# OneWireBus_Interface.net
KiCad netlist of a schematic drawn in Altium Designer
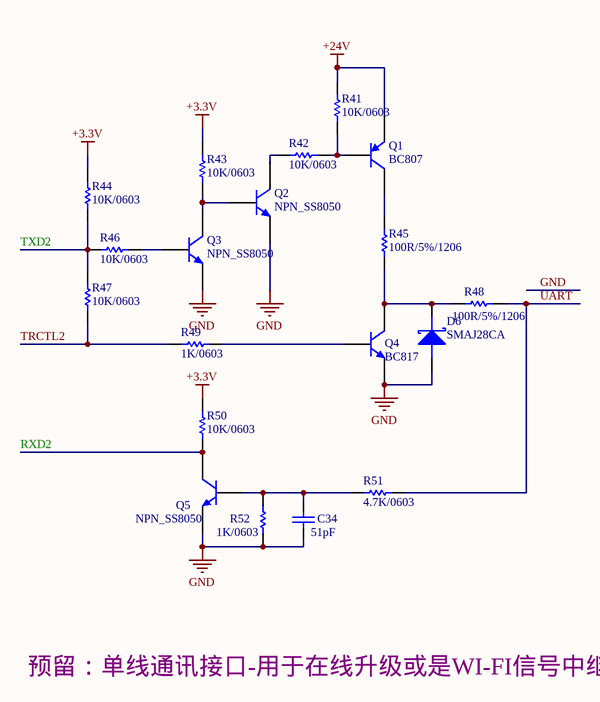
[diagram p0: OneWireBus_Interface.SchDoc]

(export (version "E")
  (design (tool "Eeschema 10.0.6"))
  (components
    (comp (ref "C34")
      (value "51pF")
      (footprint "CAP/SMT/0603C")
      (fields
        (field (name "MANUFACTURER") "Generic Components")
        (field (name "PUBLISHER") "Altium Hobart Technology Centre")
      )
      (libsource (lib "*") (part "A_Cap_0805"))
    )
    (comp (ref "D6")
      (value "SMAJ28CA")
      (footprint "D/SMT/SMBJ4.0A")
      (libsource (lib "Menred_原理图 封装库") (part "D/TVS/SMT/SMBJ6.5A/DO-214"))
    )
    (comp (ref "Q1")
      (value "BC807")
      (footprint "BJT/SMT/SOT-23")
      (description "PNP Bipolar Transistor")
      (fields (field (name "PUBLISHER") "Altium Limited"))
      (libsource (lib "ElectronIntLib") (part "PNP"))
    )
    (comp (ref "Q2")
      (value "NPN_SS8050")
      (footprint "BJT/SMT/SOT-23")
      (description "Vce25V/Vcb40V/Veb5V/Ic1.5V/Pd300mW")
      (fields (field (name "PUBLISHER") "*"))
      (libsource (lib "Menred_原理图 封装库") (part "BJT/NPN/SMT/SS8050/SOT-23"))
    )
    (comp (ref "Q3")
      (value "NPN_SS8050")
      (footprint "BJT/SMT/SOT-23")
      (description "Vce25V/Vcb40V/Veb5V/Ic1.5V/Pd300mW")
      (fields (field (name "PUBLISHER") "*"))
      (libsource (lib "Menred_原理图 封装库") (part "BJT/NPN/SMT/SS8050/SOT-23"))
    )
    (comp (ref "Q4")
      (value "BC817")
      (footprint "BJT/SMT/SOT-23")
      (description "Vce25V/Vcb40V/Veb5V/Ic1.5V/Pd300mW")
      (fields (field (name "PUBLISHER") "*"))
      (libsource (lib "Menred_原理图 封装库") (part "BJT/NPN/SMT/SS8050/SOT-23"))
    )
    (comp (ref "Q5")
      (value "NPN_SS8050")
      (footprint "BJT/SMT/SOT-23")
      (description "Vce25V/Vcb40V/Veb5V/Ic1.5V/Pd300mW")
      (fields (field (name "PUBLISHER") "*"))
      (libsource (lib "Menred_原理图 封装库") (part "BJT/NPN/SMT/SS8050/SOT-23"))
    )
    (comp (ref "R41")
      (value "10K/0603")
      (footprint "0603R")
      (description "Resistor")
      (fields
        (field (name "MANUFACTURER") "Generic Components")
        (field (name "PUBLISHER") "Altium Hobart Technology Centre")
      )
      (libsource (lib "*") (part "A_Res_0805"))
    )
    (comp (ref "R42")
      (value "10K/0603")
      (footprint "0603R")
      (description "Resistor")
      (fields
        (field (name "MANUFACTURER") "Generic Components")
        (field (name "PUBLISHER") "Altium Hobart Technology Centre")
      )
      (libsource (lib "*") (part "A_Res_0805"))
    )
    (comp (ref "R43")
      (value "10K/0603")
      (footprint "0603R")
      (description "Resistor")
      (fields
        (field (name "MANUFACTURER") "Generic Components")
        (field (name "PUBLISHER") "Altium Hobart Technology Centre")
      )
      (libsource (lib "*") (part "A_Res_0805"))
    )
    (comp (ref "R44")
      (value "10K/0603")
      (footprint "0603R")
      (description "Resistor")
      (fields
        (field (name "MANUFACTURER") "Generic Components")
        (field (name "PUBLISHER") "Altium Hobart Technology Centre")
      )
      (libsource (lib "*") (part "A_Res_0805"))
    )
    (comp (ref "R45")
      (value "100R/5%/1206")
      (footprint "1206R")
      (libsource (lib "Menred_原理图 封装库") (part "RES/RES/SMT/1206"))
    )
    (comp (ref "R46")
      (value "10K/0603")
      (footprint "0603R")
      (description "Resistor")
      (fields
        (field (name "MANUFACTURER") "Generic Components")
        (field (name "PUBLISHER") "Altium Hobart Technology Centre")
      )
      (libsource (lib "*") (part "A_Res_0805"))
    )
    (comp (ref "R47")
      (value "10K/0603")
      (footprint "0603R")
      (description "Resistor")
      (fields
        (field (name "MANUFACTURER") "Generic Components")
        (field (name "PUBLISHER") "Altium Hobart Technology Centre")
      )
      (libsource (lib "*") (part "A_Res_0805"))
    )
    (comp (ref "R48")
      (value "100R/5%/1206")
      (footprint "1206R")
      (libsource (lib "Menred_原理图 封装库") (part "RES/RES/SMT/1206"))
    )
    (comp (ref "R49")
      (value "1K/0603")
      (footprint "0603R")
      (description "Resistor")
      (fields
        (field (name "MANUFACTURER") "Generic Components")
        (field (name "PUBLISHER") "Altium Hobart Technology Centre")
      )
      (libsource (lib "*") (part "A_Res_0805"))
    )
    (comp (ref "R50")
      (value "10K/0603")
      (footprint "0603R")
      (description "Resistor")
      (fields
        (field (name "MANUFACTURER") "Generic Components")
        (field (name "PUBLISHER") "Altium Hobart Technology Centre")
      )
      (libsource (lib "*") (part "A_Res_0805"))
    )
    (comp (ref "R51")
      (value "4.7K/0603")
      (footprint "0603R")
      (description "Resistor")
      (fields
        (field (name "MANUFACTURER") "Generic Components")
        (field (name "PUBLISHER") "Altium Hobart Technology Centre")
      )
      (libsource (lib "*") (part "A_Res_0805"))
    )
    (comp (ref "R52")
      (value "1K/0603")
      (footprint "0603R")
      (description "Resistor")
      (fields
        (field (name "MANUFACTURER") "Generic Components")
        (field (name "PUBLISHER") "Altium Hobart Technology Centre")
      )
      (libsource (lib "*") (part "A_Res_0805"))
    )
  )
  (nets
    (net (code "1") (name "+3.3V") (class "Default")
      (node (ref "R43") (pin "2") (pinfunction "2_2") (pintype "passive"))
      (node (ref "R44") (pin "1") (pinfunction "1_1") (pintype "passive"))
      (node (ref "R50") (pin "2") (pinfunction "2_2") (pintype "passive"))
    )
    (net (code "2") (name "+24V") (class "Default")
      (node (ref "Q1") (pin "2") (pinfunction "E_2") (pintype "passive"))
      (node (ref "R41") (pin "2") (pinfunction "2_2") (pintype "passive"))
    )
    (net (code "3") (name "/RXD2") (class "Default")
      (node (ref "Q5") (pin "3") (pinfunction "C_3") (pintype "passive"))
      (node (ref "R50") (pin "1") (pinfunction "1_1") (pintype "passive"))
    )
    (net (code "4") (name "/TRCTL2") (class "Default")
      (node (ref "R47") (pin "2") (pinfunction "2_2") (pintype "passive"))
      (node (ref "R49") (pin "2") (pinfunction "2_2") (pintype "passive"))
    )
    (net (code "5") (name "/TXD2") (class "Default")
      (node (ref "R44") (pin "2") (pinfunction "2_2") (pintype "passive"))
      (node (ref "R46") (pin "2") (pinfunction "2_2") (pintype "passive"))
      (node (ref "R47") (pin "1") (pinfunction "1_1") (pintype "passive"))
    )
    (net (code "6") (name "/UART") (class "Default")
      (node (ref "R48") (pin "1") (pinfunction "1_1") (pintype "passive"))
      (node (ref "R51") (pin "2") (pinfunction "2_2") (pintype "passive"))
    )
    (net (code "8") (name "GND") (class "Default")
      (node (ref "C34") (pin "1") (pinfunction "1_1") (pintype "passive"))
      (node (ref "D6") (pin "1") (pinfunction "K_1") (pintype "passive"))
      (node (ref "Q2") (pin "2") (pinfunction "E_2") (pintype "passive"))
      (node (ref "Q3") (pin "2") (pinfunction "E_2") (pintype "passive"))
      (node (ref "Q4") (pin "2") (pinfunction "E_2") (pintype "passive"))
      (node (ref "Q5") (pin "2") (pinfunction "E_2") (pintype "passive"))
      (node (ref "R52") (pin "2") (pinfunction "2_2") (pintype "passive"))
    )
    (net (code "9") (name "Net-(D6-A)") (class "Default")
      (node (ref "D6") (pin "2") (pinfunction "A_2") (pintype "passive"))
      (node (ref "Q4") (pin "3") (pinfunction "C_3") (pintype "passive"))
      (node (ref "R45") (pin "1") (pinfunction "1_1") (pintype "passive"))
      (node (ref "R48") (pin "2") (pinfunction "2_2") (pintype "passive"))
    )
    (net (code "10") (name "Net-(Q1-B)") (class "Default")
      (node (ref "Q1") (pin "1") (pinfunction "B_1") (pintype "passive"))
      (node (ref "R41") (pin "1") (pinfunction "1_1") (pintype "passive"))
      (node (ref "R42") (pin "1") (pinfunction "1_1") (pintype "passive"))
    )
    (net (code "11") (name "Net-(Q1-C)") (class "Default")
      (node (ref "Q1") (pin "3") (pinfunction "C_3") (pintype "passive"))
      (node (ref "R45") (pin "2") (pinfunction "2_2") (pintype "passive"))
    )
    (net (code "12") (name "Net-(Q2-B)") (class "Default")
      (node (ref "Q2") (pin "1") (pinfunction "B_1") (pintype "passive"))
      (node (ref "Q3") (pin "3") (pinfunction "C_3") (pintype "passive"))
      (node (ref "R43") (pin "1") (pinfunction "1_1") (pintype "passive"))
    )
    (net (code "13") (name "Net-(Q2-C)") (class "Default")
      (node (ref "Q2") (pin "3") (pinfunction "C_3") (pintype "passive"))
      (node (ref "R42") (pin "2") (pinfunction "2_2") (pintype "passive"))
    )
    (net (code "14") (name "Net-(Q3-B)") (class "Default")
      (node (ref "Q3") (pin "1") (pinfunction "B_1") (pintype "passive"))
      (node (ref "R46") (pin "1") (pinfunction "1_1") (pintype "passive"))
    )
    (net (code "15") (name "Net-(Q4-B)") (class "Default")
      (node (ref "Q4") (pin "1") (pinfunction "B_1") (pintype "passive"))
      (node (ref "R49") (pin "1") (pinfunction "1_1") (pintype "passive"))
    )
    (net (code "16") (name "Net-(Q5-B)") (class "Default")
      (node (ref "C34") (pin "2") (pinfunction "2_2") (pintype "passive"))
      (node (ref "Q5") (pin "1") (pinfunction "B_1") (pintype "passive"))
      (node (ref "R51") (pin "1") (pinfunction "1_1") (pintype "passive"))
      (node (ref "R52") (pin "1") (pinfunction "1_1") (pintype "passive"))
    )
  )
)
